# Radio.net
KiCad netlist of a schematic drawn in Altium Designer
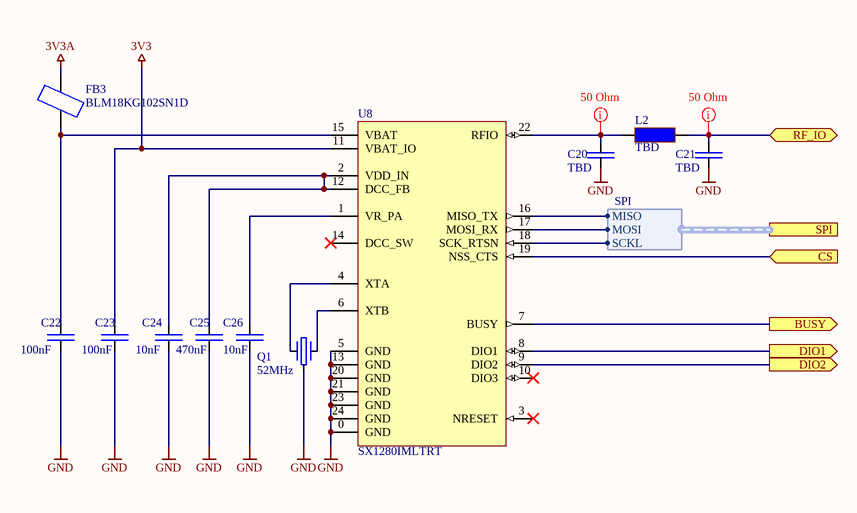
[diagram p0: Radio.SchDoc]

(export (version "E")
  (design (tool "Eeschema 10.0.6"))
  (components
    (comp (ref "C20")
      (value "TBD")
      (footprint "SMD Keramikkondensator 0402")
      (description "SMD Ceramic Capacitor E6")
      (libsource (lib "Ceramic Capacitors-E6") (part "E6 - 10pF"))
    )
    (comp (ref "C21")
      (value "TBD")
      (footprint "SMD Keramikkondensator 0402")
      (description "SMD Ceramic Capacitor E6")
      (libsource (lib "Ceramic Capacitors-E6") (part "E6 - 10pF"))
    )
    (comp (ref "C22")
      (value "100nF")
      (footprint "SMD Keramikkondensator 0603")
      (description "SMD Ceramic Capacitor E6")
      (libsource (lib "Ceramic Capacitors-E6") (part "E6 - 100nF"))
    )
    (comp (ref "C23")
      (value "100nF")
      (footprint "SMD Keramikkondensator 0603")
      (description "SMD Ceramic Capacitor E6")
      (libsource (lib "Ceramic Capacitors-E6") (part "E6 - 100nF"))
    )
    (comp (ref "C24")
      (value "10nF")
      (footprint "SMD Keramikkondensator 0603")
      (description "SMD Ceramic Capacitor E6")
      (libsource (lib "Ceramic Capacitors-E6") (part "E6 - 10nF"))
    )
    (comp (ref "C25")
      (value "470nF")
      (footprint "SMD Keramikkondensator 0603")
      (description "SMD Ceramic Capacitor E6")
      (libsource (lib "Ceramic Capacitors-E6") (part "E6 - 470nF"))
    )
    (comp (ref "C26")
      (value "10nF")
      (footprint "SMD Keramikkondensator 0603")
      (description "SMD Ceramic Capacitor E6")
      (libsource (lib "Ceramic Capacitors-E6") (part "E6 - 10nF"))
    )
    (comp (ref "FB3")
      (value "BLM18KG102SN1D")
      (footprint "SMD Ferrite Bead 0603")
      (description "1 kOhms @ 100MHz 1 Power Line Ferrite Bead 0603 (1608 Metric) 1A 200mOhm")
      (libsource (lib "Inductors") (part "BLM18KG102SN1D"))
    )
    (comp (ref "L2")
      (value "TBD")
      (footprint "SMD Ferrite Bead 0402")
      (description "Pi-Matchng Inductor")
      (libsource (lib "Inductors") (part "Inductor Pi-Matching"))
    )
    (comp (ref "Q1")
      (value "52MHz")
      (footprint "SMD Crystal 3.2X2.5X0.8")
      (description "52MHz ±7ppm Crystal 12pF 30 Ohms 4-SMD, No Lead")
      (libsource (lib "Other") (part "Crystal 52MHz - FL520WFMT1"))
    )
    (comp (ref "U8")
      (value "SX1280IMLTRT")
      (footprint "SMD IC QFN-24")
      (description "Long Range, Low Power, 2.4 GHz\r\nTransceiver with Ranging Capability")
      (libsource (lib "RF") (part "SX1280IMLTRT"))
    )
  )
  (nets
    (net (code "2") (name "/BUSY") (class "Default")
      (node (ref "U8") (pin "7") (pinfunction "BUSY_7") (pintype "output"))
    )
    (net (code "3") (name "/CS") (class "Default")
      (node (ref "U8") (pin "19") (pinfunction "NSS_CTS_19") (pintype "input"))
    )
    (net (code "4") (name "/DIO1") (class "Default")
      (node (ref "U8") (pin "8") (pinfunction "DIO1_8") (pintype "bidirectional"))
    )
    (net (code "5") (name "/DIO2") (class "Default")
      (node (ref "U8") (pin "9") (pinfunction "DIO2_9") (pintype "bidirectional"))
    )
    (net (code "6") (name "/MISO") (class "Default")
      (node (ref "U8") (pin "16") (pinfunction "MISO_TX_16") (pintype "output"))
    )
    (net (code "7") (name "/MOSI") (class "Default")
      (node (ref "U8") (pin "17") (pinfunction "MOSI_RX_17") (pintype "output"))
    )
    (net (code "8") (name "/RF_IO") (class "Default")
      (node (ref "C21") (pin "2") (pinfunction "2_2") (pintype "passive"))
      (node (ref "L2") (pin "2") (pinfunction "2_2") (pintype "passive"))
    )
    (net (code "9") (name "/SCKL") (class "Default")
      (node (ref "U8") (pin "18") (pinfunction "SCK_RTSN_18") (pintype "input"))
    )
    (net (code "11") (name "3V3") (class "Default")
      (node (ref "C23") (pin "2") (pinfunction "2_2") (pintype "passive"))
      (node (ref "U8") (pin "11") (pinfunction "VBAT_IO_11") (pintype "passive"))
    )
    (net (code "12") (name "3V3A") (class "Default")
      (node (ref "FB3") (pin "2") (pinfunction "2_2") (pintype "passive"))
    )
    (net (code "13") (name "GND") (class "Default")
      (node (ref "C20") (pin "1") (pinfunction "1_1") (pintype "passive"))
      (node (ref "C21") (pin "1") (pinfunction "1_1") (pintype "passive"))
      (node (ref "C22") (pin "1") (pinfunction "1_1") (pintype "passive"))
      (node (ref "C23") (pin "1") (pinfunction "1_1") (pintype "passive"))
      (node (ref "C24") (pin "1") (pinfunction "1_1") (pintype "passive"))
      (node (ref "C25") (pin "1") (pinfunction "1_1") (pintype "passive"))
      (node (ref "C26") (pin "1") (pinfunction "1_1") (pintype "passive"))
      (node (ref "Q1") (pin "3") (pinfunction "3_3") (pintype "power_in"))
      (node (ref "U8") (pin "0") (pinfunction "GND_0") (pintype "passive"))
      (node (ref "U8") (pin "13") (pinfunction "GND_13") (pintype "passive"))
      (node (ref "U8") (pin "20") (pinfunction "GND_20") (pintype "passive"))
      (node (ref "U8") (pin "21") (pinfunction "GND_21") (pintype "passive"))
      (node (ref "U8") (pin "23") (pinfunction "GND_23") (pintype "passive"))
      (node (ref "U8") (pin "24") (pinfunction "GND_24") (pintype "passive"))
      (node (ref "U8") (pin "5") (pinfunction "GND_5") (pintype "passive"))
    )
    (net (code "14") (name "Net-(U8-DCC_FB)") (class "Default")
      (node (ref "C24") (pin "2") (pinfunction "2_2") (pintype "passive"))
      (node (ref "C25") (pin "2") (pinfunction "2_2") (pintype "passive"))
      (node (ref "U8") (pin "12") (pinfunction "DCC_FB_12") (pintype "passive"))
      (node (ref "U8") (pin "2") (pinfunction "VDD_IN_2") (pintype "passive"))
    )
    (net (code "15") (name "Net-(U8-RFIO)") (class "Default")
      (node (ref "C20") (pin "2") (pinfunction "2_2") (pintype "passive"))
      (node (ref "L2") (pin "1") (pinfunction "1_1") (pintype "passive"))
      (node (ref "U8") (pin "22") (pinfunction "RFIO_22") (pintype "bidirectional"))
    )
    (net (code "16") (name "Net-(U8-VBAT)") (class "Default")
      (node (ref "C22") (pin "2") (pinfunction "2_2") (pintype "passive"))
      (node (ref "FB3") (pin "1") (pinfunction "1_1") (pintype "passive"))
      (node (ref "U8") (pin "15") (pinfunction "VBAT_15") (pintype "passive"))
    )
    (net (code "17") (name "Net-(U8-VR_PA)") (class "Default")
      (node (ref "C26") (pin "2") (pinfunction "2_2") (pintype "passive"))
      (node (ref "U8") (pin "1") (pinfunction "VR_PA_1") (pintype "passive"))
    )
    (net (code "18") (name "Net-(U8-XTA)") (class "Default")
      (node (ref "Q1") (pin "1") (pinfunction "1_1") (pintype "passive"))
      (node (ref "U8") (pin "4") (pinfunction "XTA_4") (pintype "passive"))
    )
    (net (code "19") (name "Net-(U8-XTB)") (class "Default")
      (node (ref "Q1") (pin "2") (pinfunction "2_2") (pintype "passive"))
      (node (ref "U8") (pin "6") (pinfunction "XTB_6") (pintype "passive"))
    )
    (net (code "20") (name "unconnected-(U8-DCC_SW-Pad14)") (class "Default")
      (node (ref "U8") (pin "14") (pinfunction "DCC_SW_14") (pintype "passive+no_connect"))
    )
    (net (code "21") (name "unconnected-(U8-DIO3-Pad10)") (class "Default")
      (node (ref "U8") (pin "10") (pinfunction "DIO3_10") (pintype "bidirectional+no_connect"))
    )
    (net (code "22") (name "unconnected-(U8-NRESET-Pad3)") (class "Default")
      (node (ref "U8") (pin "3") (pinfunction "NRESET_3") (pintype "input+no_connect"))
    )
  )
)
